# Sheet2.net
KiCad netlist of a schematic drawn in Altium Designer
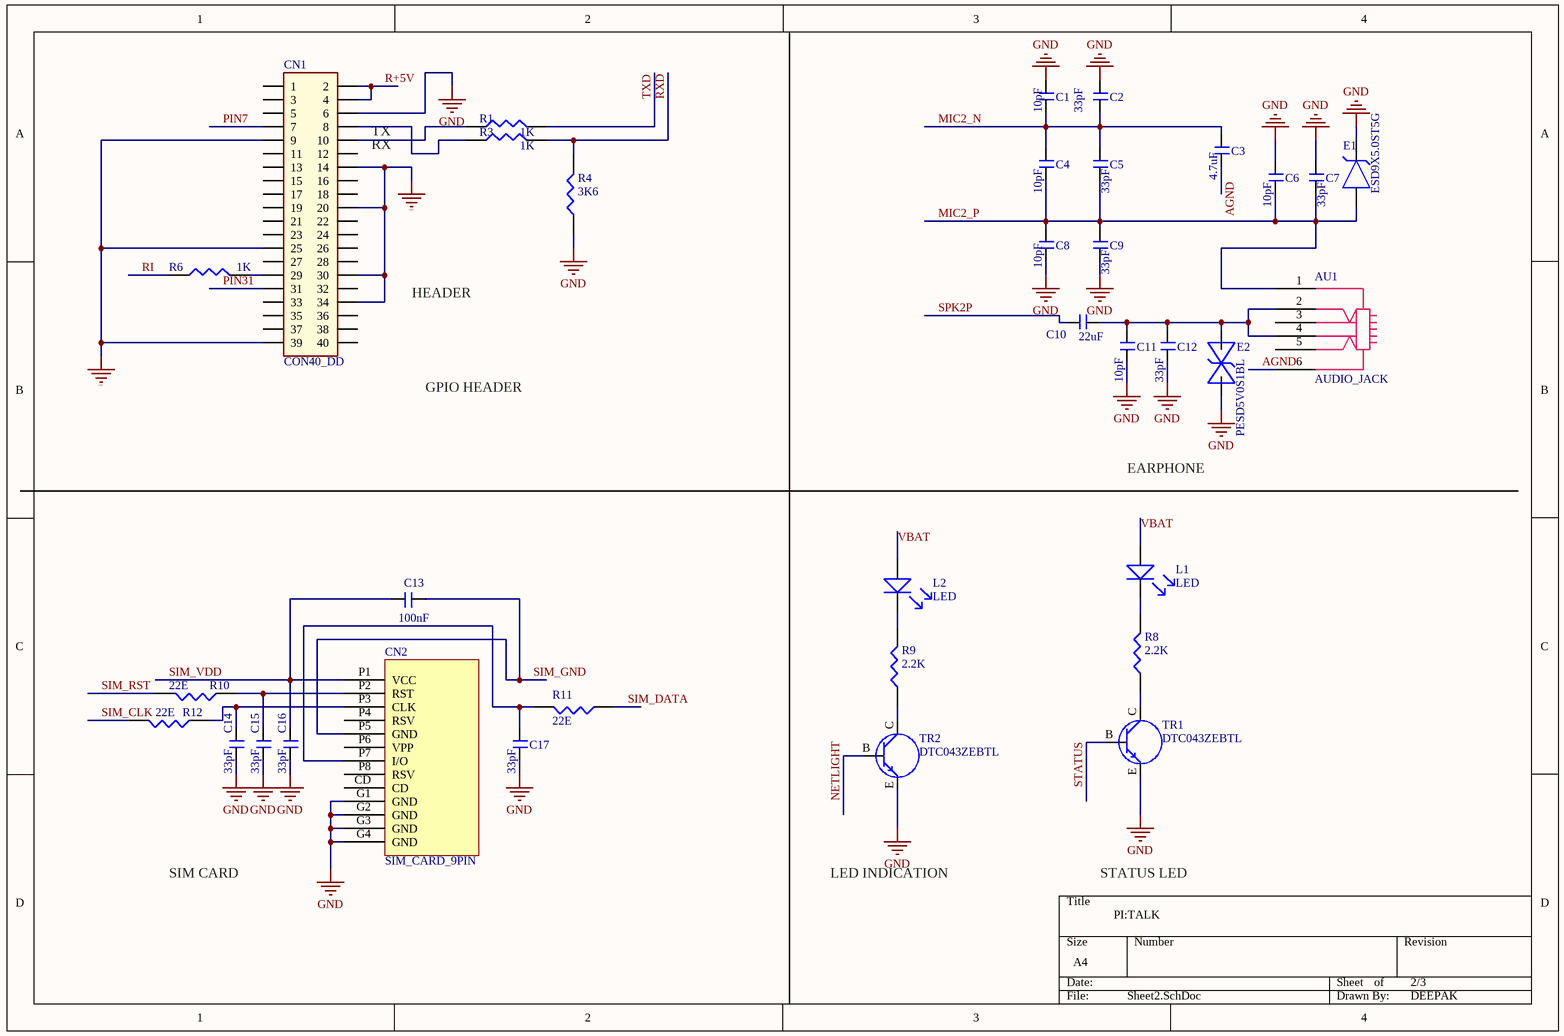
[diagram p0: Sheet2.SchDoc]

(export (version "E")
  (design (tool "Eeschema 10.0.6"))
  (components
    (comp (ref "AU1")
      (value "AUDIO_JACK")
      (footprint "EARPHONE_JACK_4183A06")
      (libsource (lib "dxp_pasl_lib") (part "EARPHONE_3.5"))
    )
    (comp (ref "C1")
      (value "10pF")
      (footprint "CAP_0603_NONPOLAR")
      (libsource (lib "dxp_pasl_lib") (part "CAP_NONPOLAR"))
    )
    (comp (ref "C2")
      (value "33pF")
      (footprint "CAP_0603_NONPOLAR")
      (libsource (lib "dxp_pasl_lib") (part "CAP_NONPOLAR"))
    )
    (comp (ref "C3")
      (value "4.7uF")
      (footprint "0805")
      (libsource (lib "dxp_pasl_lib") (part "CAP_NONPOLAR"))
    )
    (comp (ref "C4")
      (value "10pF")
      (footprint "CAP_0603_NONPOLAR")
      (libsource (lib "dxp_pasl_lib") (part "CAP_NONPOLAR"))
    )
    (comp (ref "C5")
      (value "33pF")
      (footprint "CAP_0603_NONPOLAR")
      (libsource (lib "dxp_pasl_lib") (part "CAP_NONPOLAR"))
    )
    (comp (ref "C6")
      (value "10pF")
      (footprint "CAP_0603_NONPOLAR")
      (libsource (lib "dxp_pasl_lib") (part "CAP_NONPOLAR"))
    )
    (comp (ref "C7")
      (value "33pF")
      (footprint "CAP_0603_NONPOLAR")
      (libsource (lib "dxp_pasl_lib") (part "CAP_NONPOLAR"))
    )
    (comp (ref "C8")
      (value "10pF")
      (footprint "CAP_0603_NONPOLAR")
      (libsource (lib "dxp_pasl_lib") (part "CAP_NONPOLAR"))
    )
    (comp (ref "C9")
      (value "33pF")
      (footprint "CAP_0603_NONPOLAR")
      (libsource (lib "dxp_pasl_lib") (part "CAP_NONPOLAR"))
    )
    (comp (ref "C10")
      (value "22uF")
      (footprint "CAP_0603_NONPOLAR")
      (libsource (lib "dxp_pasl_lib") (part "CAP_NONPOLAR"))
    )
    (comp (ref "C11")
      (value "10pF")
      (footprint "CAP_0603_NONPOLAR")
      (libsource (lib "dxp_pasl_lib") (part "CAP_NONPOLAR"))
    )
    (comp (ref "C12")
      (value "33pF")
      (footprint "CAP_0603_NONPOLAR")
      (libsource (lib "dxp_pasl_lib") (part "CAP_NONPOLAR"))
    )
    (comp (ref "C13")
      (value "100nF")
      (footprint "CAP_0603_NONPOLAR")
      (libsource (lib "dxp_pasl_lib") (part "CAP_NONPOLAR"))
    )
    (comp (ref "C14")
      (value "33pF")
      (footprint "CAP_0603_NONPOLAR")
      (libsource (lib "dxp_pasl_lib") (part "CAP_NONPOLAR"))
    )
    (comp (ref "C15")
      (value "33pF")
      (footprint "CAP_0603_NONPOLAR")
      (libsource (lib "dxp_pasl_lib") (part "CAP_NONPOLAR"))
    )
    (comp (ref "C16")
      (value "33pF")
      (footprint "CAP_0603_NONPOLAR")
      (libsource (lib "dxp_pasl_lib") (part "CAP_NONPOLAR"))
    )
    (comp (ref "C17")
      (value "33pF")
      (footprint "CAP_0603_NONPOLAR")
      (libsource (lib "dxp_pasl_lib") (part "CAP_NONPOLAR"))
    )
    (comp (ref "CN1")
      (value "CON40_DD")
      (footprint "CON40_DD_2p5mm")
      (libsource (lib "dxp_pasl_lib") (part "CON40_DD"))
    )
    (comp (ref "CN2")
      (value "SIM_CARD_9PIN")
      (footprint "SIM_CARD_9PIN - duplicate")
      (libsource (lib "dxp_pasl_lib") (part "SIM_CARD_9PIN"))
    )
    (comp (ref "E1")
      (value "ESD9X5.0ST5G")
      (footprint "SOD923")
      (libsource (lib "dxp_pasl_lib") (part "ESD9X5.0ST5G"))
    )
    (comp (ref "E2")
      (value "PESD5V0S1BL")
      (footprint "SOD882")
      (libsource (lib "dxp_pasl_lib") (part "PESD5V0S1BL"))
    )
    (comp (ref "L1") (value "LED") (footprint "LED_0603_neg") (libsource (lib "dxp_pasl_lib") (part "LED")))
    (comp (ref "L2") (value "LED") (footprint "LED_0603_neg") (libsource (lib "dxp_pasl_lib") (part "LED")))
    (comp (ref "R1") (value "1K") (footprint "0603") (libsource (lib "dxp_pasl_lib") (part "RES")))
    (comp (ref "R3") (value "1K") (footprint "0603") (libsource (lib "dxp_pasl_lib") (part "RES")))
    (comp (ref "R4") (value "3K6") (footprint "0603") (libsource (lib "dxp_pasl_lib") (part "RES")))
    (comp (ref "R6") (value "1K") (footprint "0603") (libsource (lib "dxp_pasl_lib") (part "RES")))
    (comp (ref "R8") (value "2.2K") (footprint "0603") (libsource (lib "dxp_pasl_lib") (part "RES")))
    (comp (ref "R9") (value "2.2K") (footprint "0603") (libsource (lib "dxp_pasl_lib") (part "RES")))
    (comp (ref "R10") (value "22E") (footprint "0603") (libsource (lib "dxp_pasl_lib") (part "RES")))
    (comp (ref "R11") (value "22E") (footprint "0603") (libsource (lib "dxp_pasl_lib") (part "RES")))
    (comp (ref "R12") (value "22E") (footprint "0603") (libsource (lib "dxp_pasl_lib") (part "RES")))
    (comp (ref "TR1")
      (value "DTC043ZEBTL")
      (footprint "DTC043ZEBTL")
      (libsource (lib "dxp_pasl_lib") (part "DTC043ZEBTL"))
    )
    (comp (ref "TR2")
      (value "DTC043ZEBTL")
      (footprint "DTC043ZEBTL")
      (libsource (lib "dxp_pasl_lib") (part "DTC043ZEBTL"))
    )
  )
  (nets
    (net (code "1") (name "/AGND") (class "Default")
      (node (ref "AU1") (pin "6") (pinfunction "+VE_6") (pintype "passive"))
      (node (ref "C3") (pin "1") (pinfunction "1_1") (pintype "passive"))
    )
    (net (code "2") (name "/MIC2_N") (class "Default")
      (node (ref "C1") (pin "1") (pinfunction "1_1") (pintype "passive"))
      (node (ref "C2") (pin "1") (pinfunction "1_1") (pintype "passive"))
      (node (ref "C3") (pin "2") (pinfunction "2_2") (pintype "passive"))
      (node (ref "C4") (pin "2") (pinfunction "2_2") (pintype "passive"))
      (node (ref "C5") (pin "2") (pinfunction "2_2") (pintype "passive"))
    )
    (net (code "3") (name "/MIC2_P") (class "Default")
      (node (ref "AU1") (pin "1") (pinfunction "GND_1") (pintype "passive"))
      (node (ref "C4") (pin "1") (pinfunction "1_1") (pintype "passive"))
      (node (ref "C5") (pin "1") (pinfunction "1_1") (pintype "passive"))
      (node (ref "C6") (pin "1") (pinfunction "1_1") (pintype "passive"))
      (node (ref "C7") (pin "1") (pinfunction "1_1") (pintype "passive"))
      (node (ref "C8") (pin "2") (pinfunction "2_2") (pintype "passive"))
      (node (ref "C9") (pin "2") (pinfunction "2_2") (pintype "passive"))
      (node (ref "E1") (pin "2") (pinfunction "A_2") (pintype "passive"))
    )
    (net (code "4") (name "/NETLIGHT") (class "Default")
      (node (ref "TR2") (pin "B") (pinfunction "B_B") (pintype "passive"))
    )
    (net (code "5") (name "/PIN7") (class "Default")
      (node (ref "CN1") (pin "7") (pinfunction "7_7") (pintype "passive"))
    )
    (net (code "6") (name "/PIN31") (class "Default")
      (node (ref "CN1") (pin "31") (pinfunction "31_31") (pintype "passive"))
    )
    (net (code "7") (name "/R+5V") (class "Default")
      (node (ref "CN1") (pin "2") (pinfunction "2_2") (pintype "passive"))
      (node (ref "CN1") (pin "4") (pinfunction "4_4") (pintype "passive"))
    )
    (net (code "8") (name "/RI") (class "Default")
      (node (ref "R6") (pin "1") (pinfunction "1_1") (pintype "passive"))
    )
    (net (code "9") (name "/RXD") (class "Default")
      (node (ref "R3") (pin "2") (pinfunction "2_2") (pintype "passive"))
      (node (ref "R4") (pin "2") (pinfunction "2_2") (pintype "passive"))
    )
    (net (code "10") (name "/SIM_CLK") (class "Default")
      (node (ref "R12") (pin "2") (pinfunction "2_2") (pintype "passive"))
    )
    (net (code "11") (name "/SIM_DATA") (class "Default")
      (node (ref "R11") (pin "1") (pinfunction "1_1") (pintype "passive"))
    )
    (net (code "12") (name "/SIM_GND") (class "Default")
      (node (ref "C13") (pin "2") (pinfunction "2_2") (pintype "passive"))
      (node (ref "CN2") (pin "P5") (pinfunction "GND_P5") (pintype "passive"))
    )
    (net (code "13") (name "/SIM_RST") (class "Default")
      (node (ref "R10") (pin "2") (pinfunction "2_2") (pintype "passive"))
    )
    (net (code "14") (name "/SIM_VDD") (class "Default")
      (node (ref "C13") (pin "1") (pinfunction "1_1") (pintype "passive"))
      (node (ref "C16") (pin "2") (pinfunction "2_2") (pintype "passive"))
      (node (ref "CN2") (pin "P1") (pinfunction "VCC_P1") (pintype "passive"))
    )
    (net (code "15") (name "/SPK2P") (class "Default")
      (node (ref "C10") (pin "2") (pinfunction "2_2") (pintype "passive"))
    )
    (net (code "16") (name "/STATUS") (class "Default")
      (node (ref "TR1") (pin "B") (pinfunction "B_B") (pintype "passive"))
    )
    (net (code "17") (name "/TXD") (class "Default")
      (node (ref "R1") (pin "2") (pinfunction "2_2") (pintype "passive"))
    )
    (net (code "18") (name "/VBAT") (class "Default")
      (node (ref "L1") (pin "A") (pinfunction "A_A") (pintype "passive"))
      (node (ref "L2") (pin "A") (pinfunction "A_A") (pintype "passive"))
    )
    (net (code "19") (name "GND") (class "Default")
      (node (ref "C1") (pin "2") (pinfunction "2_2") (pintype "passive"))
      (node (ref "C11") (pin "1") (pinfunction "1_1") (pintype "passive"))
      (node (ref "C12") (pin "1") (pinfunction "1_1") (pintype "passive"))
      (node (ref "C14") (pin "1") (pinfunction "1_1") (pintype "passive"))
      (node (ref "C15") (pin "1") (pinfunction "1_1") (pintype "passive"))
      (node (ref "C16") (pin "1") (pinfunction "1_1") (pintype "passive"))
      (node (ref "C17") (pin "1") (pinfunction "1_1") (pintype "passive"))
      (node (ref "C2") (pin "2") (pinfunction "2_2") (pintype "passive"))
      (node (ref "C6") (pin "2") (pinfunction "2_2") (pintype "passive"))
      (node (ref "C7") (pin "2") (pinfunction "2_2") (pintype "passive"))
      (node (ref "C8") (pin "1") (pinfunction "1_1") (pintype "passive"))
      (node (ref "C9") (pin "1") (pinfunction "1_1") (pintype "passive"))
      (node (ref "CN1") (pin "14") (pinfunction "14_14") (pintype "passive"))
      (node (ref "CN1") (pin "20") (pinfunction "20_20") (pintype "passive"))
      (node (ref "CN1") (pin "25") (pinfunction "25_25") (pintype "passive"))
      (node (ref "CN1") (pin "30") (pinfunction "30_30") (pintype "passive"))
      (node (ref "CN1") (pin "34") (pinfunction "34_34") (pintype "passive"))
      (node (ref "CN1") (pin "39") (pinfunction "39_39") (pintype "passive"))
      (node (ref "CN1") (pin "6") (pinfunction "6_6") (pintype "passive"))
      (node (ref "CN1") (pin "9") (pinfunction "9_9") (pintype "passive"))
      (node (ref "CN2") (pin "G1") (pinfunction "GND_G1") (pintype "passive"))
      (node (ref "CN2") (pin "G2") (pinfunction "GND_G2") (pintype "passive"))
      (node (ref "CN2") (pin "G3") (pinfunction "GND_G3") (pintype "passive"))
      (node (ref "CN2") (pin "G4") (pinfunction "GND_G4") (pintype "passive"))
      (node (ref "E1") (pin "1") (pinfunction "C_1") (pintype "passive"))
      (node (ref "E2") (pin "1") (pinfunction "C_1") (pintype "passive"))
      (node (ref "R4") (pin "1") (pinfunction "1_1") (pintype "passive"))
      (node (ref "TR1") (pin "E") (pinfunction "E_E") (pintype "passive"))
      (node (ref "TR2") (pin "E") (pinfunction "E_E") (pintype "passive"))
    )
    (net (code "20") (name "Net-(CN1-Pad8)") (class "Default")
      (node (ref "CN1") (pin "8") (pinfunction "8_8") (pintype "passive"))
      (node (ref "R3") (pin "1") (pinfunction "1_1") (pintype "passive"))
    )
    (net (code "21") (name "Net-(CN1-Pad10)") (class "Default")
      (node (ref "CN1") (pin "10") (pinfunction "10_10") (pintype "passive"))
      (node (ref "R1") (pin "1") (pinfunction "1_1") (pintype "passive"))
    )
    (net (code "22") (name "Net-(CN1-Pad29)") (class "Default")
      (node (ref "CN1") (pin "29") (pinfunction "29_29") (pintype "passive"))
      (node (ref "R6") (pin "2") (pinfunction "2_2") (pintype "passive"))
    )
    (net (code "23") (name "Net-(CN2-CLK)") (class "Default")
      (node (ref "C14") (pin "2") (pinfunction "2_2") (pintype "passive"))
      (node (ref "CN2") (pin "P3") (pinfunction "CLK_P3") (pintype "passive"))
      (node (ref "R12") (pin "1") (pinfunction "1_1") (pintype "passive"))
    )
    (net (code "24") (name "Net-(CN2-I{slash}O)") (class "Default")
      (node (ref "C17") (pin "2") (pinfunction "2_2") (pintype "passive"))
      (node (ref "CN2") (pin "P7") (pinfunction "I/O_P7") (pintype "passive"))
      (node (ref "R11") (pin "2") (pinfunction "2_2") (pintype "passive"))
    )
    (net (code "25") (name "Net-(CN2-RST)") (class "Default")
      (node (ref "C15") (pin "2") (pinfunction "2_2") (pintype "passive"))
      (node (ref "CN2") (pin "P2") (pinfunction "RST_P2") (pintype "passive"))
      (node (ref "R10") (pin "1") (pinfunction "1_1") (pintype "passive"))
    )
    (net (code "26") (name "Net-(E2-A)") (class "Default")
      (node (ref "AU1") (pin "2") (pinfunction "+VE_2") (pintype "passive"))
      (node (ref "AU1") (pin "4") (pinfunction "+VE_4") (pintype "passive"))
      (node (ref "C10") (pin "1") (pinfunction "1_1") (pintype "passive"))
      (node (ref "C11") (pin "2") (pinfunction "2_2") (pintype "passive"))
      (node (ref "C12") (pin "2") (pinfunction "2_2") (pintype "passive"))
      (node (ref "E2") (pin "2") (pinfunction "A_2") (pintype "passive"))
    )
    (net (code "27") (name "Net-(L1-PadK)") (class "Default")
      (node (ref "L1") (pin "K") (pinfunction "K_K") (pintype "passive"))
      (node (ref "R8") (pin "2") (pinfunction "2_2") (pintype "passive"))
    )
    (net (code "28") (name "Net-(L2-PadK)") (class "Default")
      (node (ref "L2") (pin "K") (pinfunction "K_K") (pintype "passive"))
      (node (ref "R9") (pin "2") (pinfunction "2_2") (pintype "passive"))
    )
    (net (code "29") (name "Net-(R8-Pad1)") (class "Default")
      (node (ref "R8") (pin "1") (pinfunction "1_1") (pintype "passive"))
      (node (ref "TR1") (pin "C") (pinfunction "C_C") (pintype "passive"))
    )
    (net (code "30") (name "Net-(R9-Pad1)") (class "Default")
      (node (ref "R9") (pin "1") (pinfunction "1_1") (pintype "passive"))
      (node (ref "TR2") (pin "C") (pinfunction "C_C") (pintype "passive"))
    )
    (net (code "31") (name "unconnected-(AU1-+VE-Pad3)") (class "Default")
      (node (ref "AU1") (pin "3") (pinfunction "+VE_3") (pintype "passive"))
    )
    (net (code "32") (name "unconnected-(AU1-+VE-Pad5)") (class "Default")
      (node (ref "AU1") (pin "5") (pinfunction "+VE_5") (pintype "passive"))
    )
    (net (code "33") (name "unconnected-(CN1-Pad1)") (class "Default")
      (node (ref "CN1") (pin "1") (pinfunction "1_1") (pintype "passive"))
    )
    (net (code "34") (name "unconnected-(CN1-Pad3)") (class "Default")
      (node (ref "CN1") (pin "3") (pinfunction "3_3") (pintype "passive"))
    )
    (net (code "35") (name "unconnected-(CN1-Pad5)") (class "Default")
      (node (ref "CN1") (pin "5") (pinfunction "5_5") (pintype "passive"))
    )
    (net (code "36") (name "unconnected-(CN1-Pad11)") (class "Default")
      (node (ref "CN1") (pin "11") (pinfunction "11_11") (pintype "passive"))
    )
    (net (code "37") (name "unconnected-(CN1-Pad12)") (class "Default")
      (node (ref "CN1") (pin "12") (pinfunction "12_12") (pintype "passive"))
    )
    (net (code "38") (name "unconnected-(CN1-Pad13)") (class "Default")
      (node (ref "CN1") (pin "13") (pinfunction "13_13") (pintype "passive"))
    )
    (net (code "39") (name "unconnected-(CN1-Pad15)") (class "Default")
      (node (ref "CN1") (pin "15") (pinfunction "15_15") (pintype "passive"))
    )
    (net (code "40") (name "unconnected-(CN1-Pad16)") (class "Default")
      (node (ref "CN1") (pin "16") (pinfunction "16_16") (pintype "passive"))
    )
    (net (code "41") (name "unconnected-(CN1-Pad17)") (class "Default")
      (node (ref "CN1") (pin "17") (pinfunction "17_17") (pintype "passive"))
    )
    (net (code "42") (name "unconnected-(CN1-Pad18)") (class "Default")
      (node (ref "CN1") (pin "18") (pinfunction "18_18") (pintype "passive"))
    )
    (net (code "43") (name "unconnected-(CN1-Pad19)") (class "Default")
      (node (ref "CN1") (pin "19") (pinfunction "19_19") (pintype "passive"))
    )
    (net (code "44") (name "unconnected-(CN1-Pad21)") (class "Default")
      (node (ref "CN1") (pin "21") (pinfunction "21_21") (pintype "passive"))
    )
    (net (code "45") (name "unconnected-(CN1-Pad22)") (class "Default")
      (node (ref "CN1") (pin "22") (pinfunction "22_22") (pintype "passive"))
    )
    (net (code "46") (name "unconnected-(CN1-Pad23)") (class "Default")
      (node (ref "CN1") (pin "23") (pinfunction "23_23") (pintype "passive"))
    )
    (net (code "47") (name "unconnected-(CN1-Pad24)") (class "Default")
      (node (ref "CN1") (pin "24") (pinfunction "24_24") (pintype "passive"))
    )
    (net (code "48") (name "unconnected-(CN1-Pad26)") (class "Default")
      (node (ref "CN1") (pin "26") (pinfunction "26_26") (pintype "passive"))
    )
    (net (code "49") (name "unconnected-(CN1-Pad27)") (class "Default")
      (node (ref "CN1") (pin "27") (pinfunction "27_27") (pintype "passive"))
    )
    (net (code "50") (name "unconnected-(CN1-Pad28)") (class "Default")
      (node (ref "CN1") (pin "28") (pinfunction "28_28") (pintype "passive"))
    )
    (net (code "51") (name "unconnected-(CN1-Pad32)") (class "Default")
      (node (ref "CN1") (pin "32") (pinfunction "32_32") (pintype "passive"))
    )
    (net (code "52") (name "unconnected-(CN1-Pad33)") (class "Default")
      (node (ref "CN1") (pin "33") (pinfunction "33_33") (pintype "passive"))
    )
    (net (code "53") (name "unconnected-(CN1-Pad35)") (class "Default")
      (node (ref "CN1") (pin "35") (pinfunction "35_35") (pintype "passive"))
    )
    (net (code "54") (name "unconnected-(CN1-Pad36)") (class "Default")
      (node (ref "CN1") (pin "36") (pinfunction "36_36") (pintype "passive"))
    )
    (net (code "55") (name "unconnected-(CN1-Pad37)") (class "Default")
      (node (ref "CN1") (pin "37") (pinfunction "37_37") (pintype "passive"))
    )
    (net (code "56") (name "unconnected-(CN1-Pad38)") (class "Default")
      (node (ref "CN1") (pin "38") (pinfunction "38_38") (pintype "passive"))
    )
    (net (code "57") (name "unconnected-(CN1-Pad40)") (class "Default")
      (node (ref "CN1") (pin "40") (pinfunction "40_40") (pintype "passive"))
    )
    (net (code "58") (name "unconnected-(CN2-PadCD)") (class "Default")
      (node (ref "CN2") (pin "CD") (pinfunction "CD_CD") (pintype "passive"))
    )
    (net (code "59") (name "unconnected-(CN2-RSV-PadP4)") (class "Default")
      (node (ref "CN2") (pin "P4") (pinfunction "RSV_P4") (pintype "passive"))
    )
    (net (code "60") (name "unconnected-(CN2-RSV-PadP8)") (class "Default")
      (node (ref "CN2") (pin "P8") (pinfunction "RSV_P8") (pintype "passive"))
    )
    (net (code "61") (name "unconnected-(CN2-VPP-PadP6)") (class "Default")
      (node (ref "CN2") (pin "P6") (pinfunction "VPP_P6") (pintype "passive"))
    )
  )
)
